# 51main.net
KiCad netlist of a schematic drawn in Altium Designer
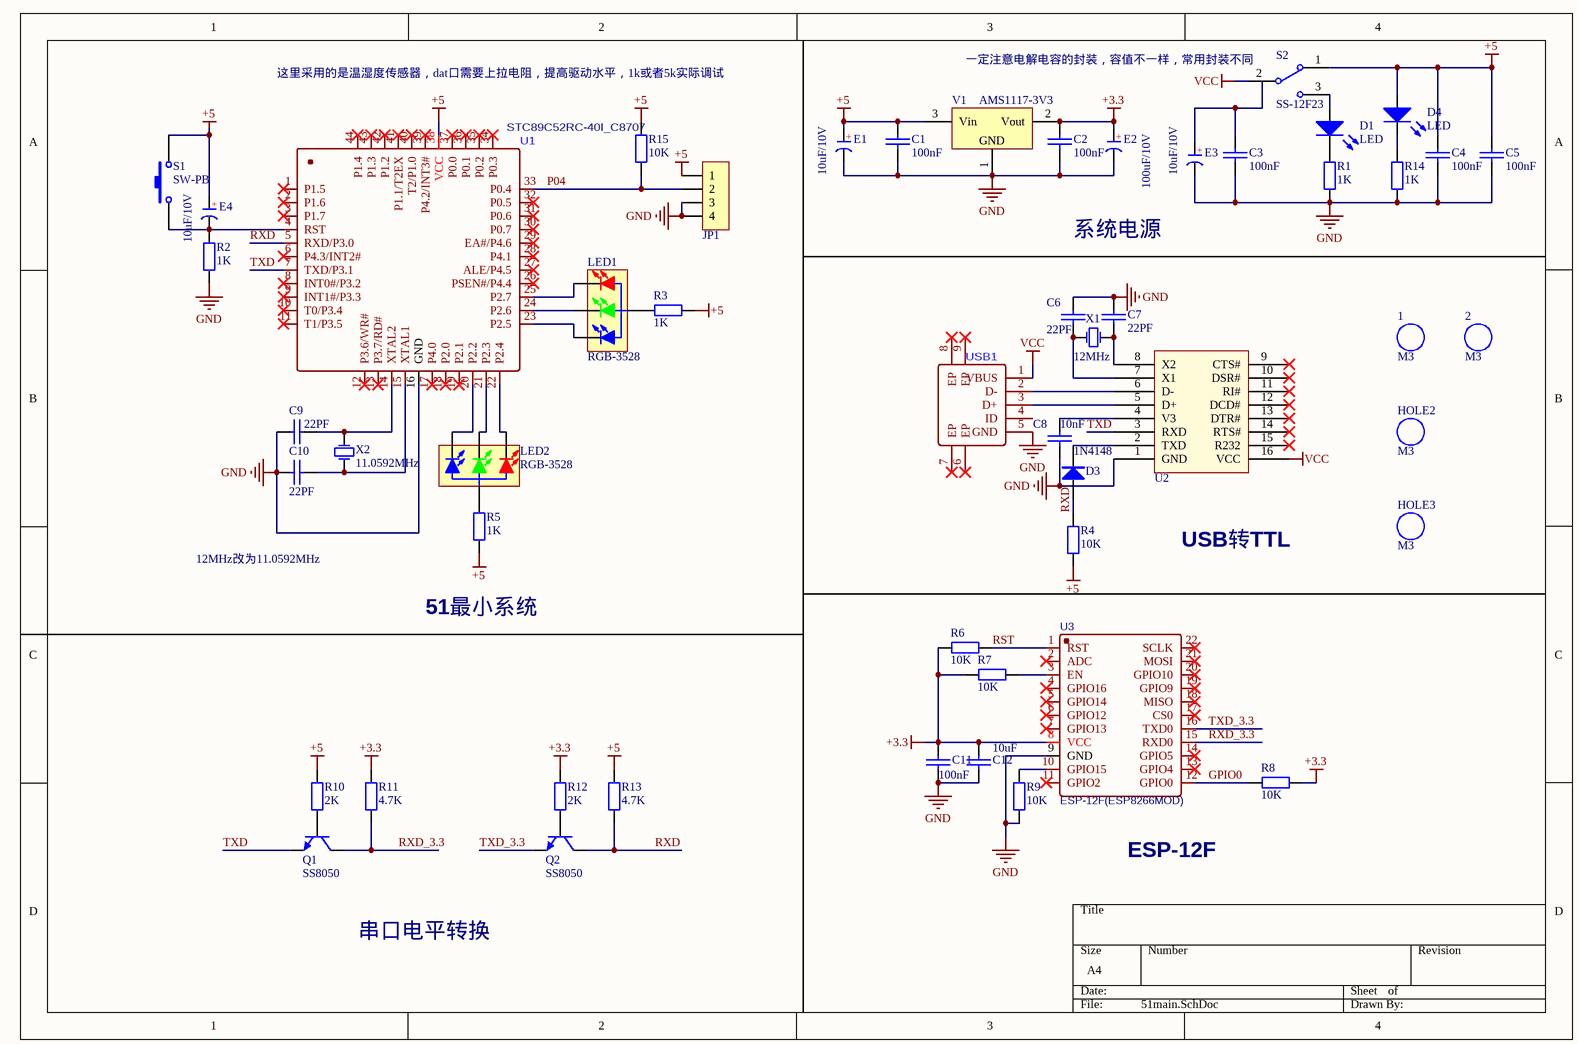
[diagram p0: 51main.SchDoc]

(export (version "E")
  (design (tool "Eeschema 10.0.6"))
  (components
    (comp (ref "1")
      (value "M3")
      (footprint "M3 125X200")
      (description "铜柱孔")
      (fields (field (name "版权归属") "封装库来自淘宝 ID：黄晶宝石"))
      (libsource (lib "4.1 - 未分类器件") (part "M3"))
    )
    (comp (ref "2")
      (value "M3")
      (footprint "M3 125X200")
      (description "铜柱孔")
      (fields (field (name "版权归属") "封装库来自淘宝 ID：黄晶宝石"))
      (libsource (lib "4.1 - 未分类器件") (part "M3"))
    )
    (comp (ref "C1")
      (value "100nF")
      (footprint "0805C")
      (description "Capacitor")
      (libsource (lib "mc") (part "CAP"))
    )
    (comp (ref "C2")
      (value "100nF")
      (footprint "0805C")
      (description "Capacitor")
      (libsource (lib "mc") (part "CAP"))
    )
    (comp (ref "C3")
      (value "100nF")
      (footprint "0805C")
      (description "Capacitor")
      (libsource (lib "mc") (part "CAP"))
    )
    (comp (ref "C4")
      (value "100nF")
      (footprint "0805C")
      (description "Capacitor")
      (libsource (lib "mc") (part "CAP"))
    )
    (comp (ref "C5")
      (value "100nF")
      (footprint "0805C")
      (description "Capacitor")
      (libsource (lib "mc") (part "CAP"))
    )
    (comp (ref "C6")
      (value "22PF")
      (footprint "0805C")
      (description "Capacitor")
      (libsource (lib "mc") (part "CAP"))
    )
    (comp (ref "C7")
      (value "22PF")
      (footprint "0805C")
      (description "Capacitor")
      (libsource (lib "mc") (part "CAP"))
    )
    (comp (ref "C8")
      (value "10nF")
      (footprint "0805C")
      (description "Capacitor")
      (libsource (lib "mc") (part "CAP"))
    )
    (comp (ref "C9")
      (value "22PF")
      (footprint "0805C")
      (description "Capacitor")
      (libsource (lib "mc") (part "CAP"))
    )
    (comp (ref "C10")
      (value "22PF")
      (footprint "0805C")
      (description "Capacitor")
      (libsource (lib "mc") (part "CAP"))
    )
    (comp (ref "C11")
      (value "100nF")
      (footprint "0805C")
      (description "Capacitor")
      (libsource (lib "mc") (part "CAP"))
    )
    (comp (ref "C12")
      (value "10uF")
      (footprint "0805C")
      (description "Capacitor")
      (libsource (lib "mc") (part "CAP"))
    )
    (comp (ref "D1")
      (value "LED")
      (footprint "0805D")
      (description "Led")
      (libsource (lib "mc") (part "LED"))
    )
    (comp (ref "D3")
      (value "1N4148")
      (footprint "SOD-323")
      (description "开关二极管")
      (libsource (lib "0.2 - 二极管-整流桥") (part "1N4148"))
    )
    (comp (ref "D4")
      (value "LED")
      (footprint "0805D")
      (description "Led")
      (libsource (lib "mc") (part "LED"))
    )
    (comp (ref "E1")
      (value "10uF/10V")
      (footprint "CM B(4*5.4)")
      (description "贴片电解电容")
      (fields (field (name "版权归属") "封装库来自淘宝 ID：黄晶宝石"))
      (libsource (lib "0.1 - 电阻-电容-电感") (part "CE_SMD"))
    )
    (comp (ref "E2")
      (value "100uF/10V")
      (footprint "CM C(5*5.4)")
      (description "贴片电解电容")
      (fields (field (name "版权归属") "封装库来自淘宝 ID：黄晶宝石"))
      (libsource (lib "0.1 - 电阻-电容-电感") (part "CE_SMD"))
    )
    (comp (ref "E3")
      (value "10uF/10V")
      (footprint "CM B(4*5.4)")
      (description "贴片电解电容")
      (fields (field (name "版权归属") "封装库来自淘宝 ID：黄晶宝石"))
      (libsource (lib "0.1 - 电阻-电容-电感") (part "CE_SMD"))
    )
    (comp (ref "E4")
      (value "10uF/10V")
      (footprint "CM B(4*5.4)")
      (description "贴片电解电容")
      (fields (field (name "版权归属") "封装库来自淘宝 ID：黄晶宝石"))
      (libsource (lib "0.1 - 电阻-电容-电感") (part "CE_SMD"))
    )
    (comp (ref "HOLE2")
      (value "M3")
      (footprint "M3 125X200")
      (description "铜柱孔")
      (fields (field (name "版权归属") "源创客"))
      (libsource (lib "STM32F407_CORE_BOARD") (part "M3"))
    )
    (comp (ref "HOLE3")
      (value "M3")
      (footprint "M3 125X200")
      (description "铜柱孔")
      (fields (field (name "版权归属") "源创客"))
      (libsource (lib "STM32F407_CORE_BOARD") (part "M3"))
    )
    (comp (ref "JP1")
      (value "HDR-1X4")
      (footprint "HDR2.54-M-LI-4P")
      (description "4P接插件")
      (fields (field (name "版权归属") "封装库来自淘宝 ID：黄晶宝石"))
      (libsource (lib "5.4 - 接插件-脚距2.54 (100mil) ") (part "Header 4"))
    )
    (comp (ref "LED1")
      (value "RGB-3528")
      (footprint "LED 3528-4Pin")
      (description "3528三基色LED")
      (fields (field (name "版权归属") "封装库来自淘宝 ID：黄晶宝石"))
      (libsource (lib "") (part "LED-RGB 3528_1"))
    )
    (comp (ref "LED2")
      (value "RGB-3528")
      (footprint "LED 3528-4Pin")
      (description "3528三基色LED")
      (fields (field (name "版权归属") "封装库来自淘宝 ID：黄晶宝石"))
      (libsource (lib "0.3 - LED发光二极管") (part "LED-RGB 3528"))
    )
    (comp (ref "Q1")
      (value "SS8050")
      (footprint "SOT23-3N")
      (description "高频放大-NPN型")
      (fields (field (name "版权归属") "封装库来自淘宝 ID：黄晶宝石"))
      (libsource (lib "0.4 - 三极管") (part "8050-SMD"))
    )
    (comp (ref "Q2")
      (value "SS8050")
      (footprint "SOT23-3N")
      (description "高频放大-NPN型")
      (fields (field (name "版权归属") "封装库来自淘宝 ID：黄晶宝石"))
      (libsource (lib "0.4 - 三极管") (part "8050-SMD"))
    )
    (comp (ref "R1")
      (value "1K")
      (footprint "R 0805_L")
      (description "贴片电阻")
      (fields (field (name "版权归属") "来自淘宝 ID：黄晶宝石"))
      (libsource (lib "0.1 - 电阻-电容-电感") (part "R"))
    )
    (comp (ref "R2")
      (value "1K")
      (footprint "R 0805_L")
      (description "贴片电阻")
      (fields (field (name "版权归属") "来自淘宝 ID：黄晶宝石"))
      (libsource (lib "0.1 - 电阻-电容-电感") (part "R"))
    )
    (comp (ref "R3")
      (value "1K")
      (footprint "R 0805_L")
      (description "贴片电阻")
      (fields (field (name "版权归属") "来自淘宝 ID：黄晶宝石"))
      (libsource (lib "0.1 - 电阻-电容-电感") (part "R"))
    )
    (comp (ref "R4")
      (value "10K")
      (footprint "R 0805_L")
      (description "贴片电阻")
      (fields (field (name "版权归属") "来自淘宝 ID：黄晶宝石"))
      (libsource (lib "0.1 - 电阻-电容-电感") (part "R"))
    )
    (comp (ref "R5")
      (value "1K")
      (footprint "R 0805_L")
      (description "贴片电阻")
      (fields (field (name "版权归属") "来自淘宝 ID：黄晶宝石"))
      (libsource (lib "0.1 - 电阻-电容-电感") (part "R"))
    )
    (comp (ref "R6")
      (value "10K")
      (footprint "R 0805_L")
      (description "贴片电阻")
      (fields (field (name "版权归属") "来自淘宝 ID：黄晶宝石"))
      (libsource (lib "0.1 - 电阻-电容-电感") (part "R"))
    )
    (comp (ref "R7")
      (value "10K")
      (footprint "R 0805_L")
      (description "贴片电阻")
      (fields (field (name "版权归属") "来自淘宝 ID：黄晶宝石"))
      (libsource (lib "0.1 - 电阻-电容-电感") (part "R"))
    )
    (comp (ref "R8")
      (value "10K")
      (footprint "R 0805_L")
      (description "贴片电阻")
      (fields (field (name "版权归属") "来自淘宝 ID：黄晶宝石"))
      (libsource (lib "0.1 - 电阻-电容-电感") (part "R"))
    )
    (comp (ref "R9")
      (value "10K")
      (footprint "R 0805_L")
      (description "贴片电阻")
      (fields (field (name "版权归属") "来自淘宝 ID：黄晶宝石"))
      (libsource (lib "0.1 - 电阻-电容-电感") (part "R"))
    )
    (comp (ref "R10")
      (value "2K")
      (footprint "R 0805_L")
      (description "贴片电阻")
      (fields (field (name "版权归属") "来自淘宝 ID：黄晶宝石"))
      (libsource (lib "0.1 - 电阻-电容-电感") (part "R"))
    )
    (comp (ref "R11")
      (value "4.7K")
      (footprint "R 0805_L")
      (description "贴片电阻")
      (fields (field (name "版权归属") "来自淘宝 ID：黄晶宝石"))
      (libsource (lib "0.1 - 电阻-电容-电感") (part "R"))
    )
    (comp (ref "R12")
      (value "2K")
      (footprint "R 0805_L")
      (description "贴片电阻")
      (fields (field (name "版权归属") "来自淘宝 ID：黄晶宝石"))
      (libsource (lib "0.1 - 电阻-电容-电感") (part "R"))
    )
    (comp (ref "R13")
      (value "4.7K")
      (footprint "R 0805_L")
      (description "贴片电阻")
      (fields (field (name "版权归属") "来自淘宝 ID：黄晶宝石"))
      (libsource (lib "0.1 - 电阻-电容-电感") (part "R"))
    )
    (comp (ref "R14")
      (value "1K")
      (footprint "R 0805_L")
      (description "贴片电阻")
      (fields (field (name "版权归属") "来自淘宝 ID：黄晶宝石"))
      (libsource (lib "0.1 - 电阻-电容-电感") (part "R"))
    )
    (comp (ref "R15")
      (value "10K")
      (footprint "R 0805_L")
      (description "贴片电阻")
      (fields (field (name "版权归属") "来自淘宝 ID：黄晶宝石"))
      (libsource (lib "0.1 - 电阻-电容-电感") (part "R"))
    )
    (comp (ref "S1")
      (value "SW-PB")
      (footprint "SW_PB2_A1")
      (description "微动开关")
      (fields (field (name "PUBLISHER") "Altium Limited"))
      (libsource (lib "0.7 - 常用按键-开关") (part "SW-PB"))
    )
    (comp (ref "S2")
      (value "SS-12F23")
      (footprint "MSK-12C01-07")
      (description "1路波动开关")
      (fields (field (name "版权归属") "封装库来自淘宝 ID：黄晶宝石"))
      (libsource (lib "0.7 - 常用按键-开关") (part "SSW-1P"))
    )
    (comp (ref "U1")
      (value "STC89C52RC-40I_C8707")
      (footprint "PCBComponent_1 - duplicate")
      (libsource (lib "STC89C52RC") (part "STC89C52RC-40I_C8707"))
    )
    (comp (ref "U2")
      (value "CH340G")
      (footprint "sop16_L")
      (libsource (lib "1.9 - CH340系列编程器芯片") (part "CH340G"))
    )
    (comp (ref "U3")
      (value "ESP-12F(ESP8266MOD)")
      (footprint "WIFIM-SMD_ESP-12F-ESP8266MOD")
      (fields (field (name "BOM_SUPPLIER PART") "C82891"))
      (libsource (lib "esp12") (part "ESP-12F(ESP8266MOD)"))
    )
    (comp (ref "USB1")
      (value "~")
      (footprint "MICRO-USB-1")
      (libsource (lib "microusb") (part "U-F-M5DS-Y-7"))
    )
    (comp (ref "V1")
      (value "AMS1117-3V3")
      (footprint "SOT223_L")
      (description "三端稳压芯片")
      (libsource (lib "1.1 - 电源类芯片") (part "AMS1117"))
    )
    (comp (ref "X1") (value "12MHz") (footprint "OSC 5032-2P") (libsource (lib "mc") (part "XTAL")))
    (comp (ref "X2") (value "11.0592MHz") (footprint "OSC 5032-2P") (libsource (lib "mc") (part "XTAL")))
  )
  (nets
    (net (code "1") (name "+3.3") (class "Default")
      (node (ref "C11") (pin "2") (pinfunction "2_2") (pintype "passive"))
      (node (ref "C12") (pin "2") (pinfunction "2_2") (pintype "passive"))
      (node (ref "C2") (pin "2") (pinfunction "2_2") (pintype "passive"))
      (node (ref "E2") (pin "1") (pinfunction "A_1") (pintype "passive"))
      (node (ref "R11") (pin "1") (pinfunction "1_1") (pintype "passive"))
      (node (ref "R12") (pin "1") (pinfunction "1_1") (pintype "passive"))
      (node (ref "R6") (pin "2") (pinfunction "2_2") (pintype "passive"))
      (node (ref "R7") (pin "2") (pinfunction "2_2") (pintype "passive"))
      (node (ref "R8") (pin "1") (pinfunction "1_1") (pintype "passive"))
      (node (ref "U3") (pin "8") (pinfunction "VCC_8") (pintype "passive"))
      (node (ref "V1") (pin "2") (pinfunction "Vout_2") (pintype "passive"))
    )
    (net (code "2") (name "+5") (class "Default")
      (node (ref "C1") (pin "2") (pinfunction "2_2") (pintype "passive"))
      (node (ref "C4") (pin "2") (pinfunction "2_2") (pintype "passive"))
      (node (ref "C5") (pin "2") (pinfunction "2_2") (pintype "passive"))
      (node (ref "D4") (pin "1") (pinfunction "A_1") (pintype "passive"))
      (node (ref "E1") (pin "1") (pinfunction "A_1") (pintype "passive"))
      (node (ref "E4") (pin "1") (pinfunction "A_1") (pintype "passive"))
      (node (ref "JP1") (pin "1") (pinfunction "1_1") (pintype "passive"))
      (node (ref "R10") (pin "1") (pinfunction "1_1") (pintype "passive"))
      (node (ref "R13") (pin "1") (pinfunction "1_1") (pintype "passive"))
      (node (ref "R15") (pin "2") (pinfunction "2_2") (pintype "passive"))
      (node (ref "R3") (pin "1") (pinfunction "1_1") (pintype "passive"))
      (node (ref "R4") (pin "1") (pinfunction "1_1") (pintype "passive"))
      (node (ref "R5") (pin "1") (pinfunction "1_1") (pintype "passive"))
      (node (ref "S1") (pin "2") (pinfunction "2_2") (pintype "passive"))
      (node (ref "S2") (pin "1") (pinfunction "1_1") (pintype "passive"))
      (node (ref "U1") (pin "38") (pinfunction "VCC_38") (pintype "passive"))
      (node (ref "V1") (pin "3") (pinfunction "Vin_3") (pintype "passive"))
    )
    (net (code "3") (name "/GPIO0") (class "Default")
      (node (ref "R8") (pin "2") (pinfunction "2_2") (pintype "passive"))
      (node (ref "U3") (pin "12") (pinfunction "GPIO0_12") (pintype "passive"))
    )
    (net (code "4") (name "/P04") (class "Default")
      (node (ref "JP1") (pin "2") (pinfunction "2_2") (pintype "passive"))
      (node (ref "R15") (pin "1") (pinfunction "1_1") (pintype "passive"))
      (node (ref "U1") (pin "33") (pinfunction "P0.4_33") (pintype "passive"))
    )
    (net (code "5") (name "/RST") (class "Default")
      (node (ref "R6") (pin "1") (pinfunction "1_1") (pintype "passive"))
      (node (ref "U3") (pin "1") (pinfunction "RST_1") (pintype "passive"))
    )
    (net (code "6") (name "/RXD") (class "Default")
      (node (ref "D3") (pin "1") (pinfunction "A_1") (pintype "passive"))
      (node (ref "Q2") (pin "3") (pinfunction "C_3") (pintype "passive"))
      (node (ref "R13") (pin "2") (pinfunction "2_2") (pintype "passive"))
      (node (ref "R4") (pin "2") (pinfunction "2_2") (pintype "passive"))
      (node (ref "U1") (pin "5") (pinfunction "RXD/P3.0_5") (pintype "passive"))
    )
    (net (code "7") (name "/RXD_3.3") (class "Default")
      (node (ref "Q1") (pin "3") (pinfunction "C_3") (pintype "passive"))
      (node (ref "R11") (pin "2") (pinfunction "2_2") (pintype "passive"))
      (node (ref "U3") (pin "15") (pinfunction "RXD0_15") (pintype "passive"))
    )
    (net (code "8") (name "/TXD") (class "Default")
      (node (ref "Q1") (pin "2") (pinfunction "E_2") (pintype "passive"))
      (node (ref "U1") (pin "7") (pinfunction "TXD/P3.1_7") (pintype "passive"))
      (node (ref "U2") (pin "3") (pinfunction "RXD_3") (pintype "passive"))
    )
    (net (code "9") (name "/TXD_3.3") (class "Default")
      (node (ref "Q2") (pin "2") (pinfunction "E_2") (pintype "passive"))
      (node (ref "U3") (pin "16") (pinfunction "TXD0_16") (pintype "passive"))
    )
    (net (code "10") (name "GND") (class "Default")
      (node (ref "C1") (pin "1") (pinfunction "1_1") (pintype "passive"))
      (node (ref "C10") (pin "1") (pinfunction "1_1") (pintype "passive"))
      (node (ref "C11") (pin "1") (pinfunction "1_1") (pintype "passive"))
      (node (ref "C12") (pin "1") (pinfunction "1_1") (pintype "passive"))
      (node (ref "C2") (pin "1") (pinfunction "1_1") (pintype "passive"))
      (node (ref "C3") (pin "1") (pinfunction "1_1") (pintype "passive"))
      (node (ref "C4") (pin "1") (pinfunction "1_1") (pintype "passive"))
      (node (ref "C5") (pin "1") (pinfunction "1_1") (pintype "passive"))
      (node (ref "C6") (pin "2") (pinfunction "2_2") (pintype "passive"))
      (node (ref "C7") (pin "2") (pinfunction "2_2") (pintype "passive"))
      (node (ref "C8") (pin "1") (pinfunction "1_1") (pintype "passive"))
      (node (ref "C9") (pin "1") (pinfunction "1_1") (pintype "passive"))
      (node (ref "E1") (pin "2") (pinfunction "K_2") (pintype "passive"))
      (node (ref "E2") (pin "2") (pinfunction "K_2") (pintype "passive"))
      (node (ref "E3") (pin "2") (pinfunction "K_2") (pintype "passive"))
      (node (ref "JP1") (pin "3") (pinfunction "3_3") (pintype "passive"))
      (node (ref "JP1") (pin "4") (pinfunction "4_4") (pintype "passive"))
      (node (ref "R1") (pin "1") (pinfunction "1_1") (pintype "passive"))
      (node (ref "R14") (pin "1") (pinfunction "1_1") (pintype "passive"))
      (node (ref "R2") (pin "1") (pinfunction "1_1") (pintype "passive"))
      (node (ref "R9") (pin "2") (pinfunction "2_2") (pintype "passive"))
      (node (ref "U1") (pin "16") (pinfunction "GND_16") (pintype "passive"))
      (node (ref "U2") (pin "1") (pinfunction "GND_1") (pintype "passive"))
      (node (ref "U3") (pin "9") (pinfunction "GND_9") (pintype "passive"))
      (node (ref "USB1") (pin "5") (pinfunction "GND_5") (pintype "passive"))
      (node (ref "V1") (pin "1") (pinfunction "GND_1") (pintype "passive"))
    )
    (net (code "11") (name "Net-(D1-A)") (class "Default")
      (node (ref "D1") (pin "1") (pinfunction "A_1") (pintype "passive"))
      (node (ref "S2") (pin "3") (pinfunction "3_3") (pintype "passive"))
    )
    (net (code "12") (name "Net-(D1-K)") (class "Default")
      (node (ref "D1") (pin "2") (pinfunction "K_2") (pintype "passive"))
      (node (ref "R1") (pin "2") (pinfunction "2_2") (pintype "passive"))
    )
    (net (code "13") (name "Net-(D3-K)") (class "Default")
      (node (ref "D3") (pin "2") (pinfunction "K_2") (pintype "passive"))
      (node (ref "U2") (pin "2") (pinfunction "TXD_2") (pintype "passive"))
    )
    (net (code "14") (name "Net-(D4-K)") (class "Default")
      (node (ref "D4") (pin "2") (pinfunction "K_2") (pintype "passive"))
      (node (ref "R14") (pin "2") (pinfunction "2_2") (pintype "passive"))
    )
    (net (code "15") (name "Net-(E3-A)") (class "Default")
      (node (ref "C3") (pin "2") (pinfunction "2_2") (pintype "passive"))
      (node (ref "E3") (pin "1") (pinfunction "A_1") (pintype "passive"))
    )
    (net (code "16") (name "Net-(E4-K)") (class "Default")
      (node (ref "E4") (pin "2") (pinfunction "K_2") (pintype "passive"))
      (node (ref "R2") (pin "2") (pinfunction "2_2") (pintype "passive"))
      (node (ref "S1") (pin "1") (pinfunction "1_1") (pintype "passive"))
      (node (ref "U1") (pin "4") (pinfunction "RST_4") (pintype "passive"))
    )
    (net (code "17") (name "Net-(LED1-A)") (class "Default")
      (node (ref "LED1") (pin "4") (pinfunction "A_4") (pintype "passive"))
      (node (ref "R3") (pin "2") (pinfunction "2_2") (pintype "passive"))
    )
    (net (code "18") (name "Net-(LED1-BULE_K)") (class "Default")
      (node (ref "LED1") (pin "3") (pinfunction "BULE_K_3") (pintype "passive"))
      (node (ref "U1") (pin "23") (pinfunction "P2.5_23") (pintype "passive"))
    )
    (net (code "19") (name "Net-(LED1-GREEN_K)") (class "Default")
      (node (ref "LED1") (pin "2") (pinfunction "GREEN_K_2") (pintype "passive"))
      (node (ref "U1") (pin "24") (pinfunction "P2.6_24") (pintype "passive"))
    )
    (net (code "20") (name "Net-(LED1-RED_K)") (class "Default")
      (node (ref "LED1") (pin "1") (pinfunction "RED_K_1") (pintype "passive"))
      (node (ref "U1") (pin "25") (pinfunction "P2.7_25") (pintype "passive"))
    )
    (net (code "21") (name "Net-(LED2-A)") (class "Default")
      (node (ref "LED2") (pin "4") (pinfunction "A_4") (pintype "passive"))
      (node (ref "R5") (pin "2") (pinfunction "2_2") (pintype "passive"))
    )
    (net (code "22") (name "Net-(LED2-BULE_K)") (class "Default")
      (node (ref "LED2") (pin "3") (pinfunction "BULE_K_3") (pintype "passive"))
      (node (ref "U1") (pin "20") (pinfunction "P2.2_20") (pintype "passive"))
    )
    (net (code "23") (name "Net-(LED2-GREEN_K)") (class "Default")
      (node (ref "LED2") (pin "2") (pinfunction "GREEN_K_2") (pintype "passive"))
      (node (ref "U1") (pin "21") (pinfunction "P2.3_21") (pintype "passive"))
    )
    (net (code "24") (name "Net-(LED2-RED_K)") (class "Default")
      (node (ref "LED2") (pin "1") (pinfunction "RED_K_1") (pintype "passive"))
      (node (ref "U1") (pin "22") (pinfunction "P2.4_22") (pintype "passive"))
    )
    (net (code "25") (name "Net-(Q1-B)") (class "Default")
      (node (ref "Q1") (pin "1") (pinfunction "B_1") (pintype "passive"))
      (node (ref "R10") (pin "2") (pinfunction "2_2") (pintype "passive"))
    )
    (net (code "26") (name "Net-(Q2-B)") (class "Default")
      (node (ref "Q2") (pin "1") (pinfunction "B_1") (pintype "passive"))
      (node (ref "R12") (pin "2") (pinfunction "2_2") (pintype "passive"))
    )
    (net (code "27") (name "Net-(U1-XTAL1)") (class "Default")
      (node (ref "C10") (pin "2") (pinfunction "2_2") (pintype "passive"))
      (node (ref "U1") (pin "15") (pinfunction "XTAL1_15") (pintype "passive"))
      (node (ref "X2") (pin "1") (pinfunction "OSC1_1") (pintype "passive"))
    )
    (net (code "28") (name "Net-(U1-XTAL2)") (class "Default")
      (node (ref "C9") (pin "2") (pinfunction "2_2") (pintype "passive"))
      (node (ref "U1") (pin "14") (pinfunction "XTAL2_14") (pintype "passive"))
      (node (ref "X2") (pin "2") (pinfunction "OSC2_2") (pintype "passive"))
    )
    (net (code "29") (name "Net-(U2-D+)") (class "Default")
      (node (ref "U2") (pin "5") (pinfunction "D+_5") (pintype "passive"))
      (node (ref "USB1") (pin "3") (pinfunction "D+_3") (pintype "passive"))
    )
    (net (code "30") (name "Net-(U2-D-)") (class "Default")
      (node (ref "U2") (pin "6") (pinfunction "D-_6") (pintype "passive"))
      (node (ref "USB1") (pin "2") (pinfunction "D-_2") (pintype "passive"))
    )
    (net (code "31") (name "Net-(U2-V3)") (class "Default")
      (node (ref "C8") (pin "2") (pinfunction "2_2") (pintype "passive"))
      (node (ref "U2") (pin "4") (pinfunction "V3_4") (pintype "passive"))
    )
    (net (code "32") (name "Net-(U2-X1)") (class "Default")
      (node (ref "C6") (pin "1") (pinfunction "1_1") (pintype "passive"))
      (node (ref "U2") (pin "7") (pinfunction "X1_7") (pintype "passive"))
      (node (ref "X1") (pin "2") (pinfunction "OSC2_2") (pintype "passive"))
    )
    (net (code "33") (name "Net-(U2-X2)") (class "Default")
      (node (ref "C7") (pin "1") (pinfunction "1_1") (pintype "passive"))
      (node (ref "U2") (pin "8") (pinfunction "X2_8") (pintype "passive"))
      (node (ref "X1") (pin "1") (pinfunction "OSC1_1") (pintype "passive"))
    )
    (net (code "34") (name "Net-(U3-EN)") (class "Default")
      (node (ref "R7") (pin "1") (pinfunction "1_1") (pintype "passive"))
      (node (ref "U3") (pin "3") (pinfunction "EN_3") (pintype "passive"))
    )
    (net (code "35") (name "Net-(U3-GPIO15)") (class "Default")
      (node (ref "R9") (pin "1") (pinfunction "1_1") (pintype "passive"))
      (node (ref "U3") (pin "10") (pinfunction "GPIO15_10") (pintype "passive"))
    )
    (net (code "36") (name "VCC") (class "Default")
      (node (ref "S2") (pin "2") (pinfunction "2_2") (pintype "passive"))
      (node (ref "U2") (pin "16") (pinfunction "VCC_16") (pintype "passive"))
      (node (ref "USB1") (pin "1") (pinfunction "VBUS_1") (pintype "passive"))
    )
    (net (code "37") (name "unconnected-(U1-ALE{slash}P4.5-Pad27)") (class "Default")
      (node (ref "U1") (pin "27") (pinfunction "ALE/P4.5_27") (pintype "passive+no_connect"))
    )
    (net (code "38") (name "unconnected-(U1-EA#{slash}P4.6-Pad29)") (class "Default")
      (node (ref "U1") (pin "29") (pinfunction "EA#/P4.6_29") (pintype "passive+no_connect"))
    )
    (net (code "39") (name "unconnected-(U1-INT0#{slash}P3.2-Pad8)") (class "Default")
      (node (ref "U1") (pin "8") (pinfunction "INT0#/P3.2_8") (pintype "passive+no_connect"))
    )
    (net (code "40") (name "unconnected-(U1-INT1#{slash}P3.3-Pad9)") (class "Default")
      (node (ref "U1") (pin "9") (pinfunction "INT1#/P3.3_9") (pintype "passive+no_connect"))
    )
    (net (code "41") (name "unconnected-(U1-P0.0-Pad37)") (class "Default")
      (node (ref "U1") (pin "37") (pinfunction "P0.0_37") (pintype "passive+no_connect"))
    )
    (net (code "42") (name "unconnected-(U1-P0.1-Pad36)") (class "Default")
      (node (ref "U1") (pin "36") (pinfunction "P0.1_36") (pintype "passive+no_connect"))
    )
    (net (code "43") (name "unconnected-(U1-P0.2-Pad35)") (class "Default")
      (node (ref "U1") (pin "35") (pinfunction "P0.2_35") (pintype "passive+no_connect"))
    )
    (net (code "44") (name "unconnected-(U1-P0.3-Pad34)") (class "Default")
      (node (ref "U1") (pin "34") (pinfunction "P0.3_34") (pintype "passive+no_connect"))
    )
    (net (code "45") (name "unconnected-(U1-P0.5-Pad32)") (class "Default")
      (node (ref "U1") (pin "32") (pinfunction "P0.5_32") (pintype "passive+no_connect"))
    )
    (net (code "46") (name "unconnected-(U1-P0.6-Pad31)") (class "Default")
      (node (ref "U1") (pin "31") (pinfunction "P0.6_31") (pintype "passive+no_connect"))
    )
    (net (code "47") (name "unconnected-(U1-P0.7-Pad30)") (class "Default")
      (node (ref "U1") (pin "30") (pinfunction "P0.7_30") (pintype "passive+no_connect"))
    )
    (net (code "48") (name "unconnected-(U1-P1.1{slash}T2EX-Pad41)") (class "Default")
      (node (ref "U1") (pin "41") (pinfunction "P1.1/T2EX_41") (pintype "passive+no_connect"))
    )
    (net (code "49") (name "unconnected-(U1-P1.2-Pad42)") (class "Default")
      (node (ref "U1") (pin "42") (pinfunction "P1.2_42") (pintype "passive+no_connect"))
    )
    (net (code "50") (name "unconnected-(U1-P1.3-Pad43)") (class "Default")
      (node (ref "U1") (pin "43") (pinfunction "P1.3_43") (pintype "passive+no_connect"))
    )
    (net (code "51") (name "unconnected-(U1-P1.4-Pad44)") (class "Default")
      (node (ref "U1") (pin "44") (pinfunction "P1.4_44") (pintype "passive+no_connect"))
    )
    (net (code "52") (name "unconnected-(U1-P1.5-Pad1)") (class "Default")
      (node (ref "U1") (pin "1") (pinfunction "P1.5_1") (pintype "passive+no_connect"))
    )
    (net (code "53") (name "unconnected-(U1-P1.6-Pad2)") (class "Default")
      (node (ref "U1") (pin "2") (pinfunction "P1.6_2") (pintype "passive+no_connect"))
    )
    (net (code "54") (name "unconnected-(U1-P1.7-Pad3)") (class "Default")
      (node (ref "U1") (pin "3") (pinfunction "P1.7_3") (pintype "passive+no_connect"))
    )
    (net (code "55") (name "unconnected-(U1-P2.0-Pad18)") (class "Default")
      (node (ref "U1") (pin "18") (pinfunction "P2.0_18") (pintype "passive+no_connect"))
    )
    (net (code "56") (name "unconnected-(U1-P2.1-Pad19)") (class "Default")
      (node (ref "U1") (pin "19") (pinfunction "P2.1_19") (pintype "passive+no_connect"))
    )
    (net (code "57") (name "unconnected-(U1-P3.6{slash}WR#-Pad12)") (class "Default")
      (node (ref "U1") (pin "12") (pinfunction "P3.6/WR#_12") (pintype "passive+no_connect"))
    )
    (net (code "58") (name "unconnected-(U1-P3.7{slash}RD#-Pad13)") (class "Default")
      (node (ref "U1") (pin "13") (pinfunction "P3.7/RD#_13") (pintype "passive+no_connect"))
    )
    (net (code "59") (name "unconnected-(U1-P4.0-Pad17)") (class "Default")
      (node (ref "U1") (pin "17") (pinfunction "P4.0_17") (pintype "passive+no_connect"))
    )
    (net (code "60") (name "unconnected-(U1-P4.1-Pad28)") (class "Default")
      (node (ref "U1") (pin "28") (pinfunction "P4.1_28") (pintype "passive+no_connect"))
    )
    (net (code "61") (name "unconnected-(U1-P4.2{slash}INT3#-Pad39)") (class "Default")
      (node (ref "U1") (pin "39") (pinfunction "P4.2/INT3#_39") (pintype "passive+no_connect"))
    )
    (net (code "62") (name "unconnected-(U1-P4.3{slash}INT2#-Pad6)") (class "Default")
      (node (ref "U1") (pin "6") (pinfunction "P4.3/INT2#_6") (pintype "passive+no_connect"))
    )
    (net (code "63") (name "unconnected-(U1-PSEN#{slash}P4.4-Pad26)") (class "Default")
      (node (ref "U1") (pin "26") (pinfunction "PSEN#/P4.4_26") (pintype "passive+no_connect"))
    )
    (net (code "64") (name "unconnected-(U1-T0{slash}P3.4-Pad10)") (class "Default")
      (node (ref "U1") (pin "10") (pinfunction "T0/P3.4_10") (pintype "passive+no_connect"))
    )
    (net (code "65") (name "unconnected-(U1-T1{slash}P3.5-Pad11)") (class "Default")
      (node (ref "U1") (pin "11") (pinfunction "T1/P3.5_11") (pintype "passive+no_connect"))
    )
    (net (code "66") (name "unconnected-(U1-T2{slash}P1.0-Pad40)") (class "Default")
      (node (ref "U1") (pin "40") (pinfunction "T2/P1.0_40") (pintype "passive+no_connect"))
    )
    (net (code "67") (name "unconnected-(U2-CTS#-Pad9)") (class "Default")
      (node (ref "U2") (pin "9") (pinfunction "CTS#_9") (pintype "passive+no_connect"))
    )
    (net (code "68") (name "unconnected-(U2-DCD#-Pad12)") (class "Default")
      (node (ref "U2") (pin "12") (pinfunction "DCD#_12") (pintype "passive+no_connect"))
    )
    (net (code "69") (name "unconnected-(U2-DSR#-Pad10)") (class "Default")
      (node (ref "U2") (pin "10") (pinfunction "DSR#_10") (pintype "passive+no_connect"))
    )
    (net (code "70") (name "unconnected-(U2-DTR#-Pad13)") (class "Default")
      (node (ref "U2") (pin "13") (pinfunction "DTR#_13") (pintype "passive+no_connect"))
    )
    (net (code "71") (name "unconnected-(U2-R232-Pad15)") (class "Default")
      (node (ref "U2") (pin "15") (pinfunction "R232_15") (pintype "passive+no_connect"))
    )
    (net (code "72") (name "unconnected-(U2-RI#-Pad11)") (class "Default")
      (node (ref "U2") (pin "11") (pinfunction "RI#_11") (pintype "passive+no_connect"))
    )
    (net (code "73") (name "unconnected-(U2-RTS#-Pad14)") (class "Default")
      (node (ref "U2") (pin "14") (pinfunction "RTS#_14") (pintype "passive+no_connect"))
    )
    (net (code "74") (name "unconnected-(U3-ADC-Pad2)") (class "Default")
      (node (ref "U3") (pin "2") (pinfunction "ADC_2") (pintype "passive+no_connect"))
    )
    (net (code "75") (name "unconnected-(U3-CS0-Pad17)") (class "Default")
      (node (ref "U3") (pin "17") (pinfunction "CS0_17") (pintype "passive+no_connect"))
    )
    (net (code "76") (name "unconnected-(U3-GPIO2-Pad11)") (class "Default")
      (node (ref "U3") (pin "11") (pinfunction "GPIO2_11") (pintype "passive+no_connect"))
    )
    (net (code "77") (name "unconnected-(U3-GPIO4-Pad13)") (class "Default")
      (node (ref "U3") (pin "13") (pinfunction "GPIO4_13") (pintype "passive+no_connect"))
    )
    (net (code "78") (name "unconnected-(U3-GPIO5-Pad14)") (class "Default")
      (node (ref "U3") (pin "14") (pinfunction "GPIO5_14") (pintype "passive+no_connect"))
    )
    (net (code "79") (name "unconnected-(U3-GPIO9-Pad19)") (class "Default")
      (node (ref "U3") (pin "19") (pinfunction "GPIO9_19") (pintype "passive+no_connect"))
    )
    (net (code "80") (name "unconnected-(U3-GPIO10-Pad20)") (class "Default")
      (node (ref "U3") (pin "20") (pinfunction "GPIO10_20") (pintype "passive+no_connect"))
    )
    (net (code "81") (name "unconnected-(U3-GPIO12-Pad6)") (class "Default")
      (node (ref "U3") (pin "6") (pinfunction "GPIO12_6") (pintype "passive+no_connect"))
    )
    (net (code "82") (name "unconnected-(U3-GPIO13-Pad7)") (class "Default")
      (node (ref "U3") (pin "7") (pinfunction "GPIO13_7") (pintype "passive+no_connect"))
    )
    (net (code "83") (name "unconnected-(U3-GPIO14-Pad5)") (class "Default")
      (node (ref "U3") (pin "5") (pinfunction "GPIO14_5") (pintype "passive+no_connect"))
    )
    (net (code "84") (name "unconnected-(U3-GPIO16-Pad4)") (class "Default")
      (node (ref "U3") (pin "4") (pinfunction "GPIO16_4") (pintype "passive+no_connect"))
    )
    (net (code "85") (name "unconnected-(U3-MISO-Pad18)") (class "Default")
      (node (ref "U3") (pin "18") (pinfunction "MISO_18") (pintype "passive+no_connect"))
    )
    (net (code "86") (name "unconnected-(U3-MOSI-Pad21)") (class "Default")
      (node (ref "U3") (pin "21") (pinfunction "MOSI_21") (pintype "passive+no_connect"))
    )
    (net (code "87") (name "unconnected-(U3-SCLK-Pad22)") (class "Default")
      (node (ref "U3") (pin "22") (pinfunction "SCLK_22") (pintype "passive+no_connect"))
    )
    (net (code "88") (name "unconnected-(USB1-EP-Pad6)") (class "Default")
      (node (ref "USB1") (pin "6") (pinfunction "EP_6") (pintype "passive+no_connect"))
    )
    (net (code "89") (name "unconnected-(USB1-EP-Pad7)") (class "Default")
      (node (ref "USB1") (pin "7") (pinfunction "EP_7") (pintype "passive+no_connect"))
    )
    (net (code "90") (name "unconnected-(USB1-EP-Pad8)") (class "Default")
      (node (ref "USB1") (pin "8") (pinfunction "EP_8") (pintype "passive+no_connect"))
    )
    (net (code "91") (name "unconnected-(USB1-EP-Pad9)") (class "Default")
      (node (ref "USB1") (pin "9") (pinfunction "EP_9") (pintype "passive+no_connect"))
    )
    (net (code "92") (name "unconnected-(USB1-ID-Pad4)") (class "Default")
      (node (ref "USB1") (pin "4") (pinfunction "ID_4") (pintype "passive"))
    )
  )
)
